# charger_0_5A.net
KiCad netlist of a schematic drawn in Altium Designer
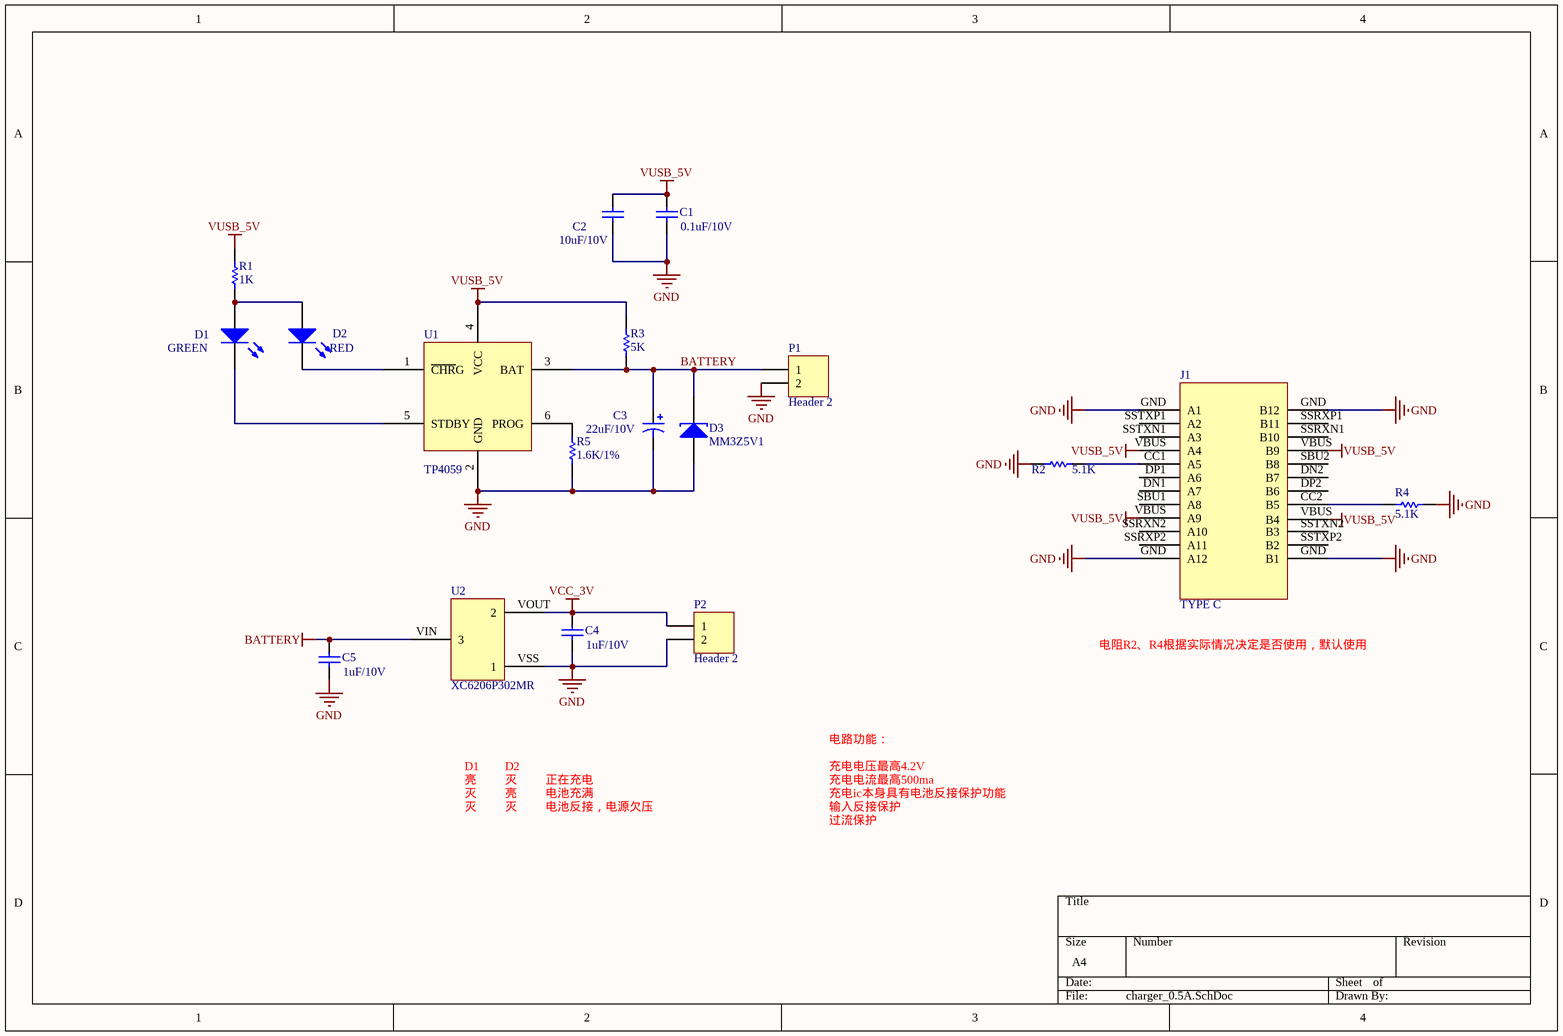
[diagram p0: charger_0.5A.SchDoc]

(export (version "E")
  (design (tool "Eeschema 10.0.6"))
  (components
    (comp (ref "C1")
      (value "0.1uF/10V")
      (footprint "0603C")
      (description "Capacitor")
      (fields (field (name "PUBLISHER") "Altium Limited"))
      (libsource (lib "Miscellaneous Devices") (part "Cap"))
    )
    (comp (ref "C2")
      (value "10uF/10V")
      (footprint "0603C")
      (description "Capacitor")
      (fields (field (name "PUBLISHER") "Altium Limited"))
      (libsource (lib "Miscellaneous Devices") (part "Cap"))
    )
    (comp (ref "C3")
      (value "22uF/10V")
      (footprint "1210E")
      (description "Polarized Capacitor (Radial)")
      (fields (field (name "PUBLISHER") "Altium Limited"))
      (libsource (lib "Miscellaneous Devices") (part "Cap Pol1"))
    )
    (comp (ref "C4")
      (value "1uF/10V")
      (footprint "0603C")
      (description "Capacitor")
      (fields (field (name "PUBLISHER") "Altium Limited"))
      (libsource (lib "Miscellaneous Devices") (part "Cap"))
    )
    (comp (ref "C5")
      (value "1uF/10V")
      (footprint "0603C")
      (description "Capacitor")
      (fields (field (name "PUBLISHER") "Altium Limited"))
      (libsource (lib "Miscellaneous Devices") (part "Cap"))
    )
    (comp (ref "D1")
      (value "~")
      (footprint "0603LED")
      (description "Typical INFRARED GaAs LED")
      (fields (field (name "PUBLISHER") "GREEN"))
      (libsource (lib "Miscellaneous Devices") (part "LED0"))
    )
    (comp (ref "D2")
      (value "~")
      (footprint "0603LED")
      (description "Typical INFRARED GaAs LED")
      (fields (field (name "PUBLISHER") "RED"))
      (libsource (lib "Miscellaneous Devices") (part "LED0"))
    )
    (comp (ref "D3")
      (value "MM3Z5V1")
      (footprint "SOD323")
      (description "Tunnel Diode - RLC Model")
      (fields (field (name "PUBLISHER") "Altium Limited"))
      (libsource (lib "Miscellaneous Devices") (part "D Tunnel1"))
    )
    (comp (ref "J1") (value "TYPE C") (libsource (lib "CHARGER") (part "TYPE C")))
    (comp (ref "P1")
      (value "Header 2")
      (footprint "HDR1X2")
      (description "Header, 2-Pin")
      (fields (field (name "PUBLISHER") "Altium Limited"))
      (libsource (lib "Miscellaneous Connectors") (part "Header 2"))
    )
    (comp (ref "P2")
      (value "Header 2")
      (footprint "HDR1X2")
      (description "Header, 2-Pin")
      (fields (field (name "PUBLISHER") "Altium Limited"))
      (libsource (lib "Miscellaneous Connectors") (part "Header 2"))
    )
    (comp (ref "R1")
      (value "1K")
      (footprint "0603R")
      (description "Semiconductor Resistor")
      (fields (field (name "PUBLISHER") "Altium Limited"))
      (libsource (lib "Miscellaneous Devices") (part "Res Semi"))
    )
    (comp (ref "R2")
      (value "5.1K")
      (footprint "0603R")
      (description "Semiconductor Resistor")
      (fields (field (name "PUBLISHER") "Altium Limited"))
      (libsource (lib "Miscellaneous Devices") (part "Res Semi"))
    )
    (comp (ref "R3")
      (value "5K")
      (footprint "0603R")
      (description "Semiconductor Resistor")
      (fields (field (name "PUBLISHER") "Altium Limited"))
      (libsource (lib "Miscellaneous Devices") (part "Res Semi"))
    )
    (comp (ref "R4")
      (value "5.1K")
      (footprint "0603R")
      (description "Semiconductor Resistor")
      (fields (field (name "PUBLISHER") "Altium Limited"))
      (libsource (lib "Miscellaneous Devices") (part "Res Semi"))
    )
    (comp (ref "R5")
      (value "1.6K/1%")
      (footprint "0603R")
      (description "Semiconductor Resistor")
      (fields (field (name "PUBLISHER") "Altium Limited"))
      (libsource (lib "Miscellaneous Devices") (part "Res Semi"))
    )
    (comp (ref "U1") (value "TP4059") (libsource (lib "CHARGER") (part "TP4059")))
    (comp (ref "U2") (value "XC6206P302MR") (libsource (lib "CHARGER") (part "XC6206P302MR")))
  )
  (nets
    (net (code "1") (name "BATTERY") (class "Default")
      (node (ref "C3") (pin "1") (pinfunction "1_1") (pintype "passive"))
      (node (ref "C5") (pin "2") (pinfunction "2_2") (pintype "passive"))
      (node (ref "D3") (pin "2") (pinfunction "K_2") (pintype "passive"))
      (node (ref "P1") (pin "1") (pinfunction "1_1") (pintype "passive"))
      (node (ref "R3") (pin "1") (pinfunction "1_1") (pintype "passive"))
      (node (ref "U1") (pin "3") (pinfunction "BAT_3") (pintype "passive"))
      (node (ref "U2") (pin "VIN") (pinfunction "3_VIN") (pintype "passive"))
    )
    (net (code "2") (name "GND") (class "Default")
      (node (ref "C1") (pin "1") (pinfunction "1_1") (pintype "passive"))
      (node (ref "C2") (pin "1") (pinfunction "1_1") (pintype "passive"))
      (node (ref "C3") (pin "2") (pinfunction "2_2") (pintype "passive"))
      (node (ref "C4") (pin "1") (pinfunction "1_1") (pintype "passive"))
      (node (ref "C5") (pin "1") (pinfunction "1_1") (pintype "passive"))
      (node (ref "D3") (pin "1") (pinfunction "A_1") (pintype "passive"))
      (node (ref "J1") (pin "GND") (pinfunction "A1_GND") (pintype "passive"))
      (node (ref "P1") (pin "2") (pinfunction "2_2") (pintype "passive"))
      (node (ref "P2") (pin "2") (pinfunction "2_2") (pintype "passive"))
      (node (ref "R2") (pin "2") (pinfunction "2_2") (pintype "passive"))
      (node (ref "R4") (pin "2") (pinfunction "2_2") (pintype "passive"))
      (node (ref "R5") (pin "1") (pinfunction "1_1") (pintype "passive"))
      (node (ref "U1") (pin "2") (pinfunction "GND_2") (pintype "passive"))
      (node (ref "U2") (pin "VSS") (pinfunction "1_VSS") (pintype "passive"))
    )
    (net (code "3") (name "Net-(D1-A)") (class "Default")
      (node (ref "D1") (pin "1") (pinfunction "A_1") (pintype "passive"))
      (node (ref "D2") (pin "1") (pinfunction "A_1") (pintype "passive"))
      (node (ref "R1") (pin "1") (pinfunction "1_1") (pintype "passive"))
    )
    (net (code "4") (name "Net-(D1-K)") (class "Default")
      (node (ref "D1") (pin "2") (pinfunction "K_2") (pintype "passive"))
      (node (ref "U1") (pin "5") (pinfunction "STDBY_5") (pintype "passive"))
    )
    (net (code "5") (name "Net-(D2-K)") (class "Default")
      (node (ref "D2") (pin "2") (pinfunction "K_2") (pintype "passive"))
      (node (ref "U1") (pin "1") (pinfunction "~{CHR}G_1") (pintype "passive"))
    )
    (net (code "6") (name "Net-(J1-A5)") (class "Default")
      (node (ref "J1") (pin "CC1") (pinfunction "A5_CC1") (pintype "passive"))
      (node (ref "R2") (pin "1") (pinfunction "1_1") (pintype "passive"))
    )
    (net (code "7") (name "Net-(J1-B5)") (class "Default")
      (node (ref "J1") (pin "CC2") (pinfunction "B5_CC2") (pintype "passive"))
      (node (ref "R4") (pin "1") (pinfunction "1_1") (pintype "passive"))
    )
    (net (code "8") (name "Net-(U1-PROG)") (class "Default")
      (node (ref "R5") (pin "2") (pinfunction "2_2") (pintype "passive"))
      (node (ref "U1") (pin "6") (pinfunction "PROG_6") (pintype "passive"))
    )
    (net (code "9") (name "VCC_3V") (class "Default")
      (node (ref "C4") (pin "2") (pinfunction "2_2") (pintype "passive"))
      (node (ref "P2") (pin "1") (pinfunction "1_1") (pintype "passive"))
      (node (ref "U2") (pin "VOUT") (pinfunction "2_VOUT") (pintype "passive"))
    )
    (net (code "10") (name "VUSB_5V") (class "Default")
      (node (ref "C1") (pin "2") (pinfunction "2_2") (pintype "passive"))
      (node (ref "C2") (pin "2") (pinfunction "2_2") (pintype "passive"))
      (node (ref "J1") (pin "VBUS") (pinfunction "A4_VBUS") (pintype "passive"))
      (node (ref "R1") (pin "2") (pinfunction "2_2") (pintype "passive"))
      (node (ref "R3") (pin "2") (pinfunction "2_2") (pintype "passive"))
      (node (ref "U1") (pin "4") (pinfunction "VCC_4") (pintype "passive"))
    )
    (net (code "11") (name "unconnected-(J1-A2-PadSSTXP1)") (class "Default")
      (node (ref "J1") (pin "SSTXP1") (pinfunction "A2_SSTXP1") (pintype "passive"))
    )
    (net (code "12") (name "unconnected-(J1-A3-PadSSTXN1)") (class "Default")
      (node (ref "J1") (pin "SSTXN1") (pinfunction "A3_SSTXN1") (pintype "passive"))
    )
    (net (code "13") (name "unconnected-(J1-A6-PadDP1)") (class "Default")
      (node (ref "J1") (pin "DP1") (pinfunction "A6_DP1") (pintype "passive"))
    )
    (net (code "14") (name "unconnected-(J1-A7-PadDN1)") (class "Default")
      (node (ref "J1") (pin "DN1") (pinfunction "A7_DN1") (pintype "passive"))
    )
    (net (code "15") (name "unconnected-(J1-A8-PadSBU1)") (class "Default")
      (node (ref "J1") (pin "SBU1") (pinfunction "A8_SBU1") (pintype "passive"))
    )
    (net (code "16") (name "unconnected-(J1-A10-PadSSRXN2)") (class "Default")
      (node (ref "J1") (pin "SSRXN2") (pinfunction "A10_SSRXN2") (pintype "passive"))
    )
    (net (code "17") (name "unconnected-(J1-A11-PadSSRXP2)") (class "Default")
      (node (ref "J1") (pin "SSRXP2") (pinfunction "A11_SSRXP2") (pintype "passive"))
    )
    (net (code "18") (name "unconnected-(J1-B2-PadSSTXP2)") (class "Default")
      (node (ref "J1") (pin "SSTXP2") (pinfunction "B2_SSTXP2") (pintype "passive"))
    )
    (net (code "19") (name "unconnected-(J1-B3-PadSSTXN2)") (class "Default")
      (node (ref "J1") (pin "SSTXN2") (pinfunction "B3_SSTXN2") (pintype "passive"))
    )
    (net (code "20") (name "unconnected-(J1-B6-PadDP2)") (class "Default")
      (node (ref "J1") (pin "DP2") (pinfunction "B6_DP2") (pintype "passive"))
    )
    (net (code "21") (name "unconnected-(J1-B7-PadDN2)") (class "Default")
      (node (ref "J1") (pin "DN2") (pinfunction "B7_DN2") (pintype "passive"))
    )
    (net (code "22") (name "unconnected-(J1-B8-PadSBU2)") (class "Default")
      (node (ref "J1") (pin "SBU2") (pinfunction "B8_SBU2") (pintype "passive"))
    )
    (net (code "23") (name "unconnected-(J1-B10-PadSSRXN1)") (class "Default")
      (node (ref "J1") (pin "SSRXN1") (pinfunction "B10_SSRXN1") (pintype "passive"))
    )
    (net (code "24") (name "unconnected-(J1-B11-PadSSRXP1)") (class "Default")
      (node (ref "J1") (pin "SSRXP1") (pinfunction "B11_SSRXP1") (pintype "passive"))
    )
  )
)
